# SensorStation_Board_v0_5.net
KiCad netlist of a schematic drawn in EAGLE
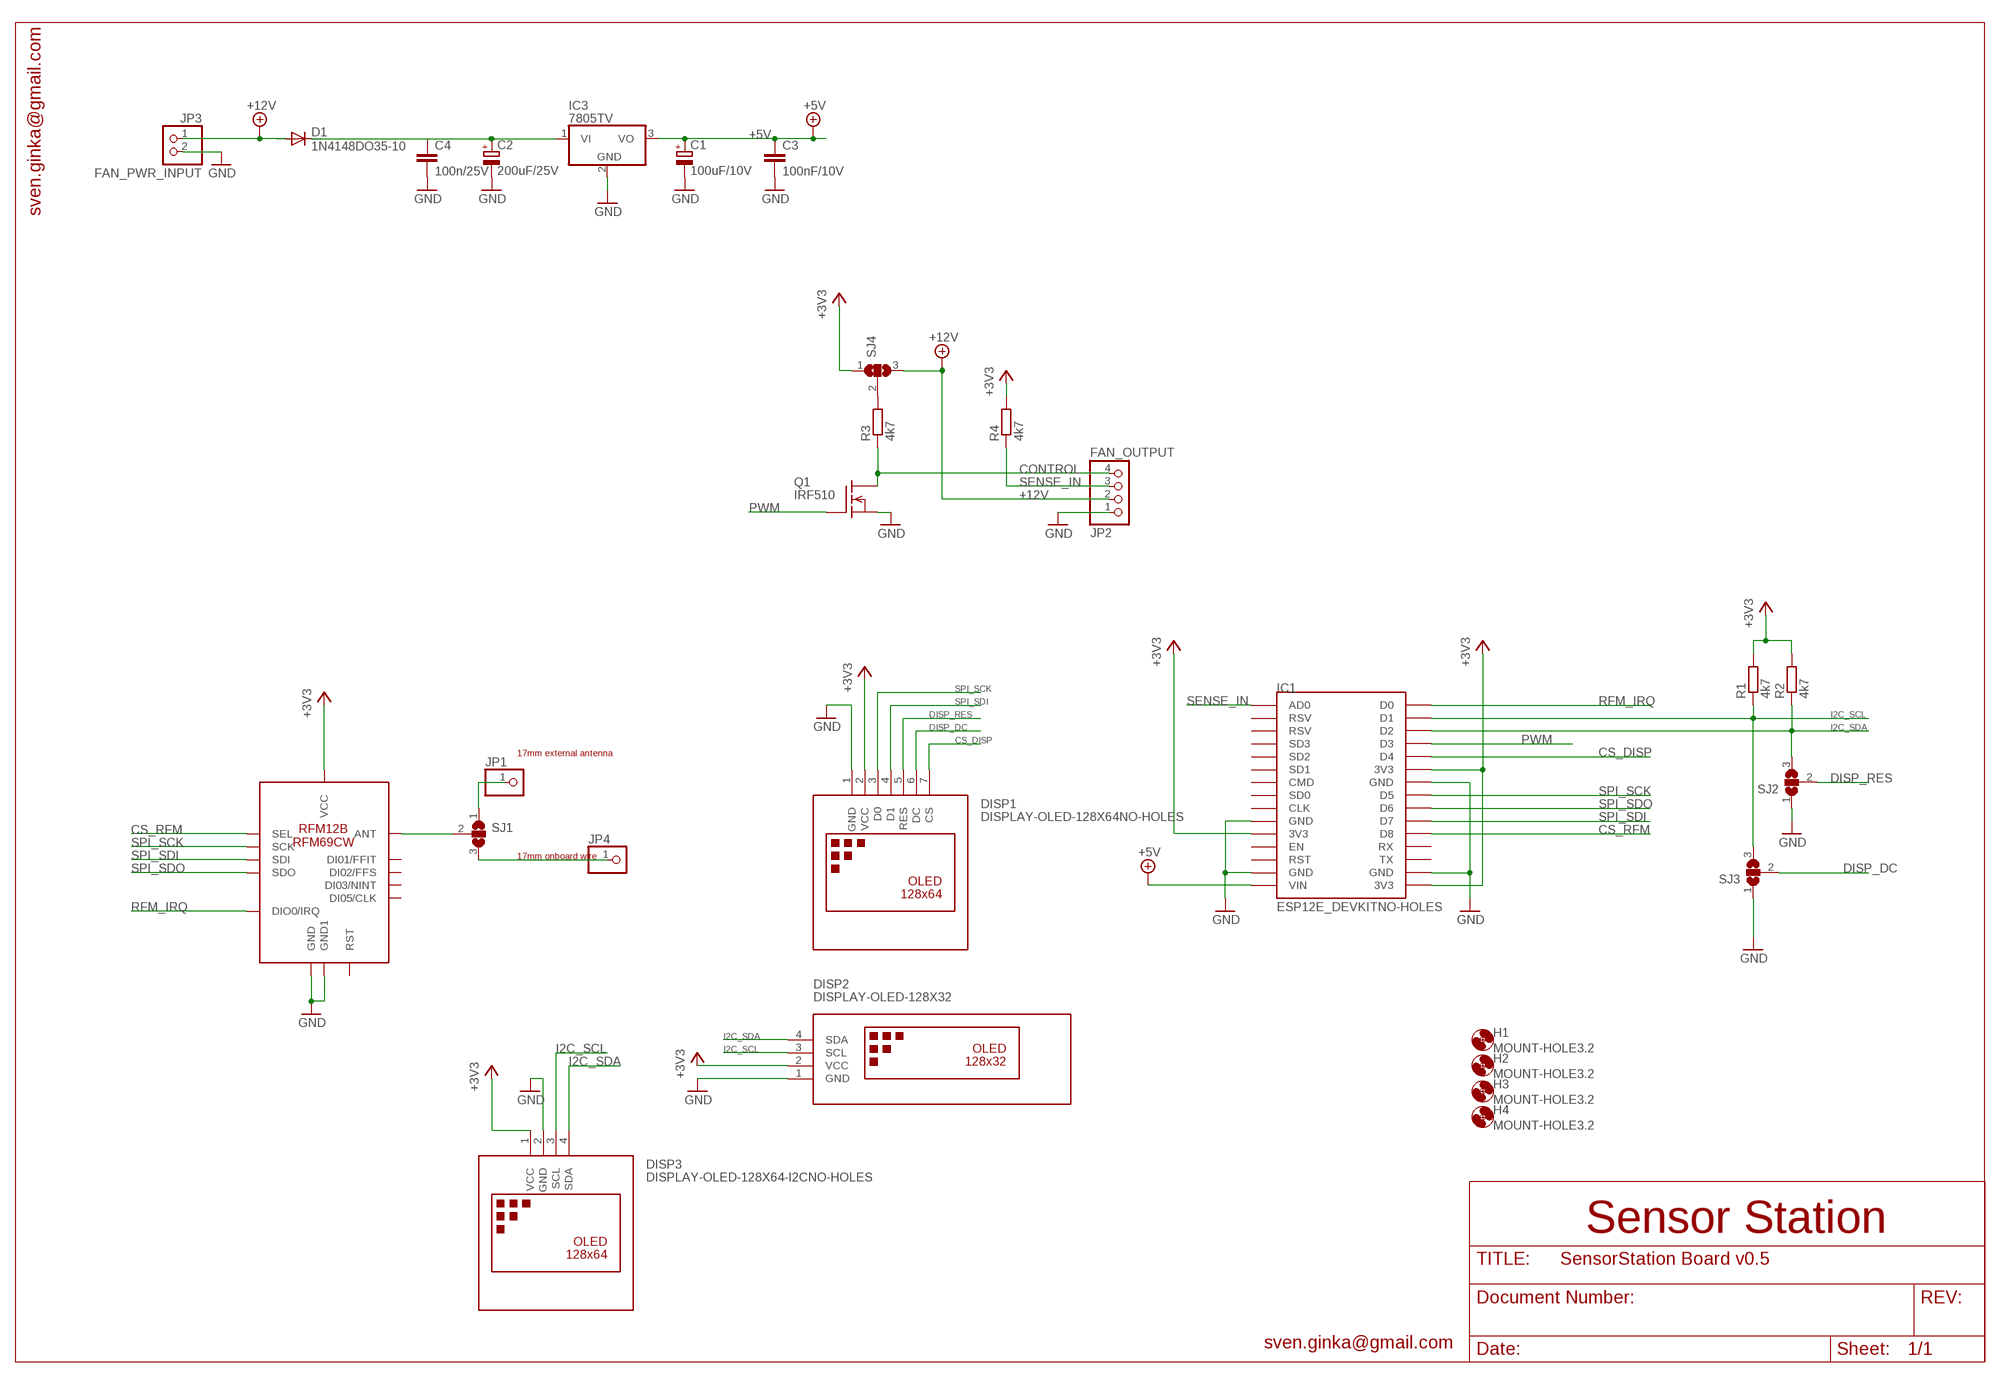
[diagram p0: schematic, sheet 1]

(export (version "E")
  (design (tool "Eeschema 10.0.6"))
  (components
    (comp (ref "C1")
      (value "100uF/10V")
      (footprint "eagle-import:E2,5-6")
      (libsource (lib "eagle-import") (part "CPOL-EUE2.5-6"))
    )
    (comp (ref "C2")
      (value "200uF/25V")
      (footprint "eagle-import:E2,5-6")
      (libsource (lib "eagle-import") (part "CPOL-EUE2.5-6"))
    )
    (comp (ref "C3")
      (value "100nF/10V")
      (footprint "eagle-import:C025-025X050")
      (libsource (lib "eagle-import") (part "C-EU025-025X050"))
    )
    (comp (ref "C4")
      (value "100n/25V")
      (footprint "eagle-import:C025-025X050")
      (libsource (lib "eagle-import") (part "C-EU025-025X050"))
    )
    (comp (ref "D1")
      (value "1N4148DO35-10")
      (footprint "eagle-import:DO35-10")
      (libsource (lib "eagle-import") (part "1N4148DO35-10"))
    )
    (comp (ref "DISP1")
      (value "DISPLAY-OLED-128X64NO-HOLES")
      (footprint "eagle-import:DISPLAY-OLED-128X64-NO-HOLES")
      (libsource (lib "eagle-import") (part "DISPLAY-OLED-128X64NO-HOLES"))
    )
    (comp (ref "DISP2")
      (value "DISPLAY-OLED-128X32")
      (footprint "eagle-import:DISPLAY-OLED-128X32")
      (libsource (lib "eagle-import") (part "DISPLAY-OLED-128X32"))
    )
    (comp (ref "DISP3")
      (value "DISPLAY-OLED-128X64-I2CNO-HOLES")
      (footprint "eagle-import:DISPLAY-OLED-128X64-I2C-NO-HOLES")
      (libsource (lib "eagle-import") (part "DISPLAY-OLED-128X64-I2CNO-HOLES"))
    )
    (comp (ref "H1")
      (value "MOUNT-HOLE3.2")
      (footprint "eagle-import:3,2")
      (libsource (lib "eagle-import") (part "MOUNT-HOLE3.2"))
    )
    (comp (ref "H2")
      (value "MOUNT-HOLE3.2")
      (footprint "eagle-import:3,2")
      (libsource (lib "eagle-import") (part "MOUNT-HOLE3.2"))
    )
    (comp (ref "H3")
      (value "MOUNT-HOLE3.2")
      (footprint "eagle-import:3,2")
      (libsource (lib "eagle-import") (part "MOUNT-HOLE3.2"))
    )
    (comp (ref "H4")
      (value "MOUNT-HOLE3.2")
      (footprint "eagle-import:3,2")
      (libsource (lib "eagle-import") (part "MOUNT-HOLE3.2"))
    )
    (comp (ref "IC1")
      (value "ESP12E_DEVKITNO-HOLES")
      (footprint "eagle-import:ESP12E_DEVKIT-NO-HOLES")
      (libsource (lib "eagle-import") (part "ESP12E_DEVKITNO-HOLES"))
    )
    (comp (ref "IC2")
      (value "RFM12B/69CW")
      (footprint "eagle-import:RFM12B_69CW")
      (libsource (lib "eagle-import") (part "RFM12B/69CW"))
    )
    (comp (ref "IC3")
      (value "7805TV")
      (footprint "eagle-import:TO220V")
      (libsource (lib "eagle-import") (part "78TV05"))
    )
    (comp (ref "JP1")
      (value "PINHD-1X1")
      (footprint "eagle-import:1X01")
      (libsource (lib "eagle-import") (part "PINHD-1X1"))
    )
    (comp (ref "JP2")
      (value "FAN_OUTPUT")
      (footprint "eagle-import:1X04")
      (libsource (lib "eagle-import") (part "PINHD-1X4"))
    )
    (comp (ref "JP3")
      (value "FAN_PWR_INPUT")
      (footprint "eagle-import:1X02")
      (libsource (lib "eagle-import") (part "PINHD-1X2"))
    )
    (comp (ref "JP4")
      (value "PINHD-1X1")
      (footprint "eagle-import:1X01")
      (libsource (lib "eagle-import") (part "PINHD-1X1"))
    )
    (comp (ref "Q1")
      (value "IRF510")
      (footprint "eagle-import:TO220")
      (libsource (lib "eagle-import") (part "IRF510"))
    )
    (comp (ref "R1")
      (value "4k7")
      (footprint "eagle-import:0204_5")
      (libsource (lib "eagle-import") (part "R-EU_0204/5"))
    )
    (comp (ref "R2")
      (value "4k7")
      (footprint "eagle-import:0204_5")
      (libsource (lib "eagle-import") (part "R-EU_0204/5"))
    )
    (comp (ref "R3")
      (value "4k7")
      (footprint "eagle-import:0204_5")
      (libsource (lib "eagle-import") (part "R-EU_0204/5"))
    )
    (comp (ref "R4")
      (value "4k7")
      (footprint "eagle-import:0204_5")
      (libsource (lib "eagle-import") (part "R-EU_0204/5"))
    )
    (comp (ref "SJ1")
      (value "SJ2W")
      (footprint "eagle-import:SJ_2")
      (libsource (lib "eagle-import") (part "SJ2W"))
    )
    (comp (ref "SJ2")
      (value "SJ2W")
      (footprint "eagle-import:SJ_2")
      (libsource (lib "eagle-import") (part "SJ2W"))
    )
    (comp (ref "SJ3")
      (value "SJ2W")
      (footprint "eagle-import:SJ_2")
      (libsource (lib "eagle-import") (part "SJ2W"))
    )
    (comp (ref "SJ4")
      (value "SJ2W")
      (footprint "eagle-import:SJ_2")
      (libsource (lib "eagle-import") (part "SJ2W"))
    )
  )
  (nets
    (net (code "1") (name "+3V3") (class "Default")
      (node (ref "DISP1") (pin "2") (pinfunction "VCC_2") (pintype "power_in"))
      (node (ref "DISP2") (pin "2") (pinfunction "VCC_2") (pintype "power_in"))
      (node (ref "DISP3") (pin "1") (pinfunction "VCC_1") (pintype "power_in"))
      (node (ref "IC1") (pin "3V3@0") (pinfunction "3V3_3V3@0") (pintype "bidirectional"))
      (node (ref "IC1") (pin "3V3@1") (pinfunction "3V3_3V3@1") (pintype "bidirectional"))
      (node (ref "IC1") (pin "3V3@2") (pinfunction "3V3_3V3@2") (pintype "bidirectional"))
      (node (ref "IC2") (pin "VDD") (pinfunction "VCC_VDD") (pintype "power_in"))
      (node (ref "R1") (pin "2") (pinfunction "2_2") (pintype "passive"))
      (node (ref "R2") (pin "2") (pinfunction "2_2") (pintype "passive"))
      (node (ref "R4") (pin "2") (pinfunction "2_2") (pintype "passive"))
      (node (ref "SJ4") (pin "1") (pinfunction "1_1") (pintype "passive"))
    )
    (net (code "2") (name "+5V") (class "Default")
      (node (ref "C1") (pin "+") (pinfunction "+_+") (pintype "passive"))
      (node (ref "C3") (pin "1") (pinfunction "1_1") (pintype "passive"))
      (node (ref "IC1") (pin "VIN") (pinfunction "VIN_VIN") (pintype "bidirectional"))
      (node (ref "IC3") (pin "3") (pinfunction "VO_3") (pintype "passive"))
    )
    (net (code "3") (name "+12V") (class "Default")
      (node (ref "D1") (pin "A") (pinfunction "A_A") (pintype "passive"))
      (node (ref "JP2") (pin "2") (pinfunction "2_2") (pintype "passive"))
      (node (ref "JP3") (pin "1") (pinfunction "1_1") (pintype "passive"))
      (node (ref "SJ4") (pin "3") (pinfunction "3_3") (pintype "passive"))
    )
    (net (code "4") (name "/CONTROL") (class "Default")
      (node (ref "JP2") (pin "4") (pinfunction "4_4") (pintype "passive"))
      (node (ref "Q1") (pin "2") (pinfunction "D_2") (pintype "passive"))
      (node (ref "R3") (pin "1") (pinfunction "1_1") (pintype "passive"))
    )
    (net (code "5") (name "/CS_DISP") (class "Default")
      (node (ref "DISP1") (pin "7") (pinfunction "CS_7") (pintype "bidirectional"))
      (node (ref "IC1") (pin "D4") (pinfunction "D4_D4") (pintype "bidirectional"))
    )
    (net (code "6") (name "/CS_RFM") (class "Default")
      (node (ref "IC1") (pin "D8") (pinfunction "D8_D8") (pintype "bidirectional"))
      (node (ref "IC2") (pin "SEL") (pinfunction "SEL_SEL") (pintype "input"))
    )
    (net (code "7") (name "/DISP_DC") (class "Default")
      (node (ref "DISP1") (pin "6") (pinfunction "DC_6") (pintype "bidirectional"))
      (node (ref "SJ3") (pin "2") (pinfunction "2_2") (pintype "passive"))
    )
    (net (code "8") (name "/DISP_RES") (class "Default")
      (node (ref "DISP1") (pin "5") (pinfunction "RES_5") (pintype "bidirectional"))
      (node (ref "SJ2") (pin "2") (pinfunction "2_2") (pintype "passive"))
    )
    (net (code "9") (name "/I2C_SCL") (class "Default")
      (node (ref "DISP2") (pin "3") (pinfunction "SCL_3") (pintype "bidirectional"))
      (node (ref "DISP3") (pin "3") (pinfunction "SCL_3") (pintype "bidirectional"))
      (node (ref "IC1") (pin "D1") (pinfunction "D1_D1") (pintype "bidirectional"))
      (node (ref "R1") (pin "1") (pinfunction "1_1") (pintype "passive"))
      (node (ref "SJ3") (pin "3") (pinfunction "3_3") (pintype "passive"))
    )
    (net (code "10") (name "/I2C_SDA") (class "Default")
      (node (ref "DISP2") (pin "4") (pinfunction "SDA_4") (pintype "bidirectional"))
      (node (ref "DISP3") (pin "4") (pinfunction "SDA_4") (pintype "bidirectional"))
      (node (ref "IC1") (pin "D2") (pinfunction "D2_D2") (pintype "bidirectional"))
      (node (ref "R2") (pin "1") (pinfunction "1_1") (pintype "passive"))
      (node (ref "SJ2") (pin "3") (pinfunction "3_3") (pintype "passive"))
    )
    (net (code "11") (name "/PWM") (class "Default")
      (node (ref "IC1") (pin "D3") (pinfunction "D3_D3") (pintype "bidirectional"))
      (node (ref "Q1") (pin "1") (pinfunction "G_1") (pintype "passive"))
    )
    (net (code "12") (name "/RFM_IRQ") (class "Default")
      (node (ref "IC1") (pin "D0") (pinfunction "D0_D0") (pintype "bidirectional"))
      (node (ref "IC2") (pin "IRQ") (pinfunction "DIO0/IRQ_IRQ") (pintype "open_collector"))
    )
    (net (code "13") (name "/SENSE_IN") (class "Default")
      (node (ref "IC1") (pin "AD0") (pinfunction "AD0_AD0") (pintype "bidirectional"))
      (node (ref "JP2") (pin "3") (pinfunction "3_3") (pintype "passive"))
      (node (ref "R4") (pin "1") (pinfunction "1_1") (pintype "passive"))
    )
    (net (code "14") (name "/SPI_SCK") (class "Default")
      (node (ref "DISP1") (pin "3") (pinfunction "D0_3") (pintype "bidirectional"))
      (node (ref "IC1") (pin "D5") (pinfunction "D5_D5") (pintype "bidirectional"))
      (node (ref "IC2") (pin "SCK") (pinfunction "SCK_SCK") (pintype "input"))
    )
    (net (code "15") (name "/SPI_SDI") (class "Default")
      (node (ref "DISP1") (pin "4") (pinfunction "D1_4") (pintype "bidirectional"))
      (node (ref "IC1") (pin "D7") (pinfunction "D7_D7") (pintype "bidirectional"))
      (node (ref "IC2") (pin "SDI") (pinfunction "SDI_SDI") (pintype "input"))
    )
    (net (code "16") (name "/SPI_SDO") (class "Default")
      (node (ref "IC1") (pin "D6") (pinfunction "D6_D6") (pintype "bidirectional"))
      (node (ref "IC2") (pin "SDO") (pinfunction "SDO_SDO") (pintype "output"))
    )
    (net (code "17") (name "GND") (class "Default")
      (node (ref "C1") (pin "-") (pinfunction "-_-") (pintype "passive"))
      (node (ref "C2") (pin "-") (pinfunction "-_-") (pintype "passive"))
      (node (ref "C3") (pin "2") (pinfunction "2_2") (pintype "passive"))
      (node (ref "C4") (pin "2") (pinfunction "2_2") (pintype "passive"))
      (node (ref "DISP1") (pin "1") (pinfunction "GND_1") (pintype "power_in"))
      (node (ref "DISP2") (pin "1") (pinfunction "GND_1") (pintype "power_in"))
      (node (ref "DISP3") (pin "2") (pinfunction "GND_2") (pintype "power_in"))
      (node (ref "IC1") (pin "GND@0") (pinfunction "GND_GND@0") (pintype "bidirectional"))
      (node (ref "IC1") (pin "GND@1") (pinfunction "GND_GND@1") (pintype "bidirectional"))
      (node (ref "IC1") (pin "GND@2") (pinfunction "GND_GND@2") (pintype "bidirectional"))
      (node (ref "IC1") (pin "GND@3") (pinfunction "GND_GND@3") (pintype "bidirectional"))
      (node (ref "IC2") (pin "GND") (pinfunction "GND_GND") (pintype "power_in"))
      (node (ref "IC2") (pin "GND1") (pinfunction "GND1_GND1") (pintype "power_in"))
      (node (ref "IC3") (pin "2") (pinfunction "GND_2") (pintype "passive"))
      (node (ref "JP2") (pin "1") (pinfunction "1_1") (pintype "passive"))
      (node (ref "JP3") (pin "2") (pinfunction "2_2") (pintype "passive"))
      (node (ref "Q1") (pin "3") (pinfunction "S_3") (pintype "passive"))
      (node (ref "SJ2") (pin "1") (pinfunction "1_1") (pintype "passive"))
      (node (ref "SJ3") (pin "1") (pinfunction "1_1") (pintype "passive"))
    )
    (net (code "18") (name "Net-(IC2-PadANT)") (class "Default")
      (node (ref "IC2") (pin "ANT") (pinfunction "ANT_ANT") (pintype "passive"))
      (node (ref "SJ1") (pin "2") (pinfunction "2_2") (pintype "passive"))
    )
    (net (code "19") (name "Net-(IC3-VI)") (class "Default")
      (node (ref "C2") (pin "+") (pinfunction "+_+") (pintype "passive"))
      (node (ref "C4") (pin "1") (pinfunction "1_1") (pintype "passive"))
      (node (ref "D1") (pin "C") (pinfunction "C_C") (pintype "passive"))
      (node (ref "IC3") (pin "1") (pinfunction "VI_1") (pintype "input"))
    )
    (net (code "20") (name "Net-(JP1-Pad1)") (class "Default")
      (node (ref "JP1") (pin "1") (pinfunction "1_1") (pintype "passive"))
      (node (ref "SJ1") (pin "1") (pinfunction "1_1") (pintype "passive"))
    )
    (net (code "21") (name "Net-(JP4-Pad1)") (class "Default")
      (node (ref "JP4") (pin "1") (pinfunction "1_1") (pintype "passive"))
      (node (ref "SJ1") (pin "3") (pinfunction "3_3") (pintype "passive"))
    )
    (net (code "22") (name "Net-(R3-Pad2)") (class "Default")
      (node (ref "R3") (pin "2") (pinfunction "2_2") (pintype "passive"))
      (node (ref "SJ4") (pin "2") (pinfunction "2_2") (pintype "passive"))
    )
    (net (code "23") (name "unconnected-(IC1-PadCLK)") (class "Default")
      (node (ref "IC1") (pin "CLK") (pinfunction "CLK_CLK") (pintype "bidirectional"))
    )
    (net (code "24") (name "unconnected-(IC1-PadCMD)") (class "Default")
      (node (ref "IC1") (pin "CMD") (pinfunction "CMD_CMD") (pintype "bidirectional"))
    )
    (net (code "25") (name "unconnected-(IC1-PadEN)") (class "Default")
      (node (ref "IC1") (pin "EN") (pinfunction "EN_EN") (pintype "bidirectional"))
    )
    (net (code "26") (name "unconnected-(IC1-PadRST)") (class "Default")
      (node (ref "IC1") (pin "RST") (pinfunction "RST_RST") (pintype "bidirectional"))
    )
    (net (code "27") (name "unconnected-(IC1-PadRX)") (class "Default")
      (node (ref "IC1") (pin "RX") (pinfunction "RX_RX") (pintype "bidirectional"))
    )
    (net (code "28") (name "unconnected-(IC1-PadSD0)") (class "Default")
      (node (ref "IC1") (pin "SD0") (pinfunction "SD0_SD0") (pintype "bidirectional"))
    )
    (net (code "29") (name "unconnected-(IC1-PadSD1)") (class "Default")
      (node (ref "IC1") (pin "SD1") (pinfunction "SD1_SD1") (pintype "bidirectional"))
    )
    (net (code "30") (name "unconnected-(IC1-PadSD2)") (class "Default")
      (node (ref "IC1") (pin "SD2") (pinfunction "SD2_SD2") (pintype "bidirectional"))
    )
    (net (code "31") (name "unconnected-(IC1-PadSD3)") (class "Default")
      (node (ref "IC1") (pin "SD3") (pinfunction "SD3_SD3") (pintype "bidirectional"))
    )
    (net (code "32") (name "unconnected-(IC1-PadTX)") (class "Default")
      (node (ref "IC1") (pin "TX") (pinfunction "TX_TX") (pintype "bidirectional"))
    )
    (net (code "33") (name "unconnected-(IC1-RSV-PadRSV@0)") (class "Default")
      (node (ref "IC1") (pin "RSV@0") (pinfunction "RSV_RSV@0") (pintype "bidirectional"))
    )
    (net (code "34") (name "unconnected-(IC1-RSV-PadRSV@1)") (class "Default")
      (node (ref "IC1") (pin "RSV@1") (pinfunction "RSV_RSV@1") (pintype "bidirectional"))
    )
    (net (code "35") (name "unconnected-(IC2-DI01{slash}FFIT-PadFFIT)") (class "Default")
      (node (ref "IC2") (pin "FFIT") (pinfunction "DI01/FFIT_FFIT") (pintype "passive"))
    )
    (net (code "36") (name "unconnected-(IC2-DI02{slash}FFS-PadFFS)") (class "Default")
      (node (ref "IC2") (pin "FFS") (pinfunction "DI02/FFS_FFS") (pintype "bidirectional"))
    )
    (net (code "37") (name "unconnected-(IC2-DI03{slash}NINT-PadNINT)") (class "Default")
      (node (ref "IC2") (pin "NINT") (pinfunction "DI03/NINT_NINT") (pintype "passive"))
    )
    (net (code "38") (name "unconnected-(IC2-DI05{slash}CLK-PadCLK)") (class "Default")
      (node (ref "IC2") (pin "CLK") (pinfunction "DI05/CLK_CLK") (pintype "passive"))
    )
    (net (code "39") (name "unconnected-(IC2-PadRST)") (class "Default")
      (node (ref "IC2") (pin "RST") (pinfunction "RST_RST") (pintype "open_collector"))
    )
  )
)
